# CAN_Switch.net
KiCad netlist of a schematic drawn in Altium Designer
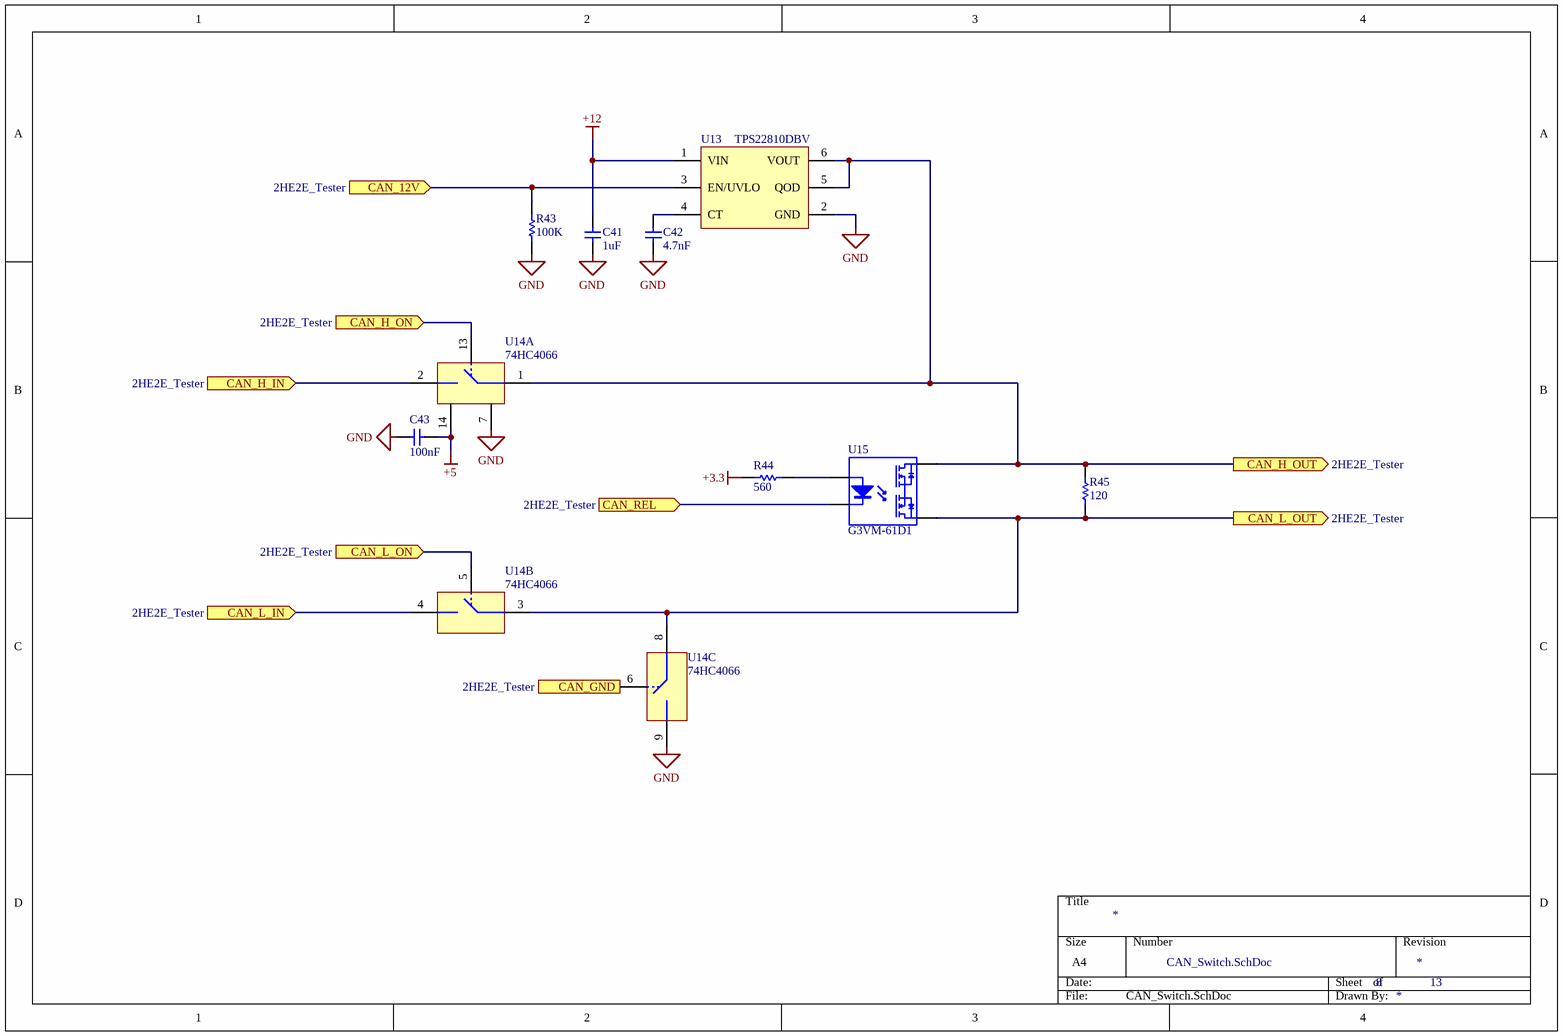
[diagram p0: CAN_Switch.SchDoc]

(export (version "E")
  (design (tool "Eeschema 10.0.6"))
  (components
    (comp (ref "C41")
      (value "1uF")
      (footprint "0603M-C")
      (description "Ceramic Capacitor 16V")
      (fields (field (name "Comment") "Cap Ceramic"))
      (libsource (lib "Plume") (part "Cap Ceramic"))
    )
    (comp (ref "C42")
      (value "4.7nF")
      (footprint "0603M-C")
      (description "Ceramic Capacitor")
      (fields (field (name "Comment") "Cap Ceramic"))
      (libsource (lib "Plume") (part "Cap Ceramic"))
    )
    (comp (ref "C43")
      (value "100nF")
      (footprint "0603M-C")
      (description "Ceramic Capacitor")
      (fields (field (name "Comment") "Cap Ceramic"))
      (libsource (lib "Plume") (part "Cap Ceramic"))
    )
    (comp (ref "R43")
      (value "100K")
      (footprint "0603M")
      (description "Resistor")
      (libsource (lib "Plume") (part "Resistor"))
    )
    (comp (ref "R44")
      (value "560")
      (footprint "0603M")
      (description "Resistor")
      (libsource (lib "Plume") (part "Resistor"))
    )
    (comp (ref "R45")
      (value "120")
      (footprint "0603M")
      (description "Resistor")
      (libsource (lib "Plume") (part "Resistor"))
    )
    (comp (ref "U13")
      (value "TPS22810DBV")
      (footprint "SOT23-6 (SOT26)")
      (description "Load Switch With Thermal Protection 2.7-18-V, 79-mΩ On-Resistance")
      (libsource (lib "Plume") (part "TPS22810DBV"))
    )
    (comp (ref "U14")
      (value "74HC4066")
      (footprint "SOIC127P600X175-14N-Medium Density")
      (description "Quad bilateral switch")
      (libsource (lib "") (part "74HC4066_1"))
    )
    (comp (ref "U15")
      (value "G3VM-61D1")
      (footprint "G3VM-351D")
      (description "FotoMOS FET Relays")
      (libsource (lib "Plume") (part "FotoMOS"))
    )
  )
  (nets
    (net (code "1") (name "+3.3") (class "Default")
      (node (ref "R44") (pin "2") (pinfunction "2_2") (pintype "passive"))
    )
    (net (code "2") (name "+5") (class "Default")
      (node (ref "C43") (pin "2") (pinfunction "2_2") (pintype "passive"))
      (node (ref "U14") (pin "14") (pinfunction "VCC_14") (pintype "power_in"))
    )
    (net (code "3") (name "+12") (class "Default")
      (node (ref "C41") (pin "1") (pinfunction "1_1") (pintype "passive"))
      (node (ref "U13") (pin "1") (pinfunction "VIN_1") (pintype "passive"))
    )
    (net (code "4") (name "/CAN_12V") (class "Default")
      (node (ref "R43") (pin "2") (pinfunction "2_2") (pintype "passive"))
      (node (ref "U13") (pin "3") (pinfunction "EN/UVLO_3") (pintype "passive"))
    )
    (net (code "5") (name "/CAN_GND") (class "Default")
      (node (ref "U14") (pin "6") (pinfunction "6_6") (pintype "passive"))
    )
    (net (code "6") (name "/CAN_H_IN") (class "Default")
      (node (ref "U14") (pin "2") (pinfunction "2_2") (pintype "passive"))
    )
    (net (code "7") (name "/CAN_H_ON") (class "Default")
      (node (ref "U14") (pin "13") (pinfunction "13_13") (pintype "passive"))
    )
    (net (code "8") (name "/CAN_H_OUT") (class "Default")
      (node (ref "R45") (pin "2") (pinfunction "2_2") (pintype "passive"))
      (node (ref "U13") (pin "5") (pinfunction "QOD_5") (pintype "passive"))
      (node (ref "U13") (pin "6") (pinfunction "VOUT_6") (pintype "passive"))
      (node (ref "U14") (pin "1") (pinfunction "1_1") (pintype "passive"))
      (node (ref "U15") (pin "4") (pinfunction "MOS+_4") (pintype "passive"))
    )
    (net (code "9") (name "/CAN_L_IN") (class "Default")
      (node (ref "U14") (pin "4") (pinfunction "4_4") (pintype "passive"))
    )
    (net (code "10") (name "/CAN_L_ON") (class "Default")
      (node (ref "U14") (pin "5") (pinfunction "5_5") (pintype "passive"))
    )
    (net (code "11") (name "/CAN_L_OUT") (class "Default")
      (node (ref "R45") (pin "1") (pinfunction "1_1") (pintype "passive"))
      (node (ref "U14") (pin "3") (pinfunction "3_3") (pintype "passive"))
      (node (ref "U14") (pin "8") (pinfunction "8_8") (pintype "passive"))
      (node (ref "U15") (pin "3") (pinfunction "MOS-_3") (pintype "passive"))
    )
    (net (code "12") (name "/CAN_REL") (class "Default")
      (node (ref "U15") (pin "2") (pinfunction "K_2") (pintype "passive"))
    )
    (net (code "13") (name "GND") (class "Default")
      (node (ref "C41") (pin "2") (pinfunction "2_2") (pintype "passive"))
      (node (ref "C42") (pin "2") (pinfunction "2_2") (pintype "passive"))
      (node (ref "C43") (pin "1") (pinfunction "1_1") (pintype "passive"))
      (node (ref "R43") (pin "1") (pinfunction "1_1") (pintype "passive"))
      (node (ref "U13") (pin "2") (pinfunction "GND_2") (pintype "passive"))
      (node (ref "U14") (pin "7") (pinfunction "GND_7") (pintype "power_in"))
      (node (ref "U14") (pin "9") (pinfunction "9_9") (pintype "passive"))
    )
    (net (code "14") (name "Net-(U13-CT)") (class "Default")
      (node (ref "C42") (pin "1") (pinfunction "1_1") (pintype "passive"))
      (node (ref "U13") (pin "4") (pinfunction "CT_4") (pintype "passive"))
    )
    (net (code "15") (name "Net-(U15-A)") (class "Default")
      (node (ref "R44") (pin "1") (pinfunction "1_1") (pintype "passive"))
      (node (ref "U15") (pin "1") (pinfunction "A_1") (pintype "passive"))
    )
  )
)
